# rizon_io.net
KiCad netlist of a schematic drawn in EAGLE
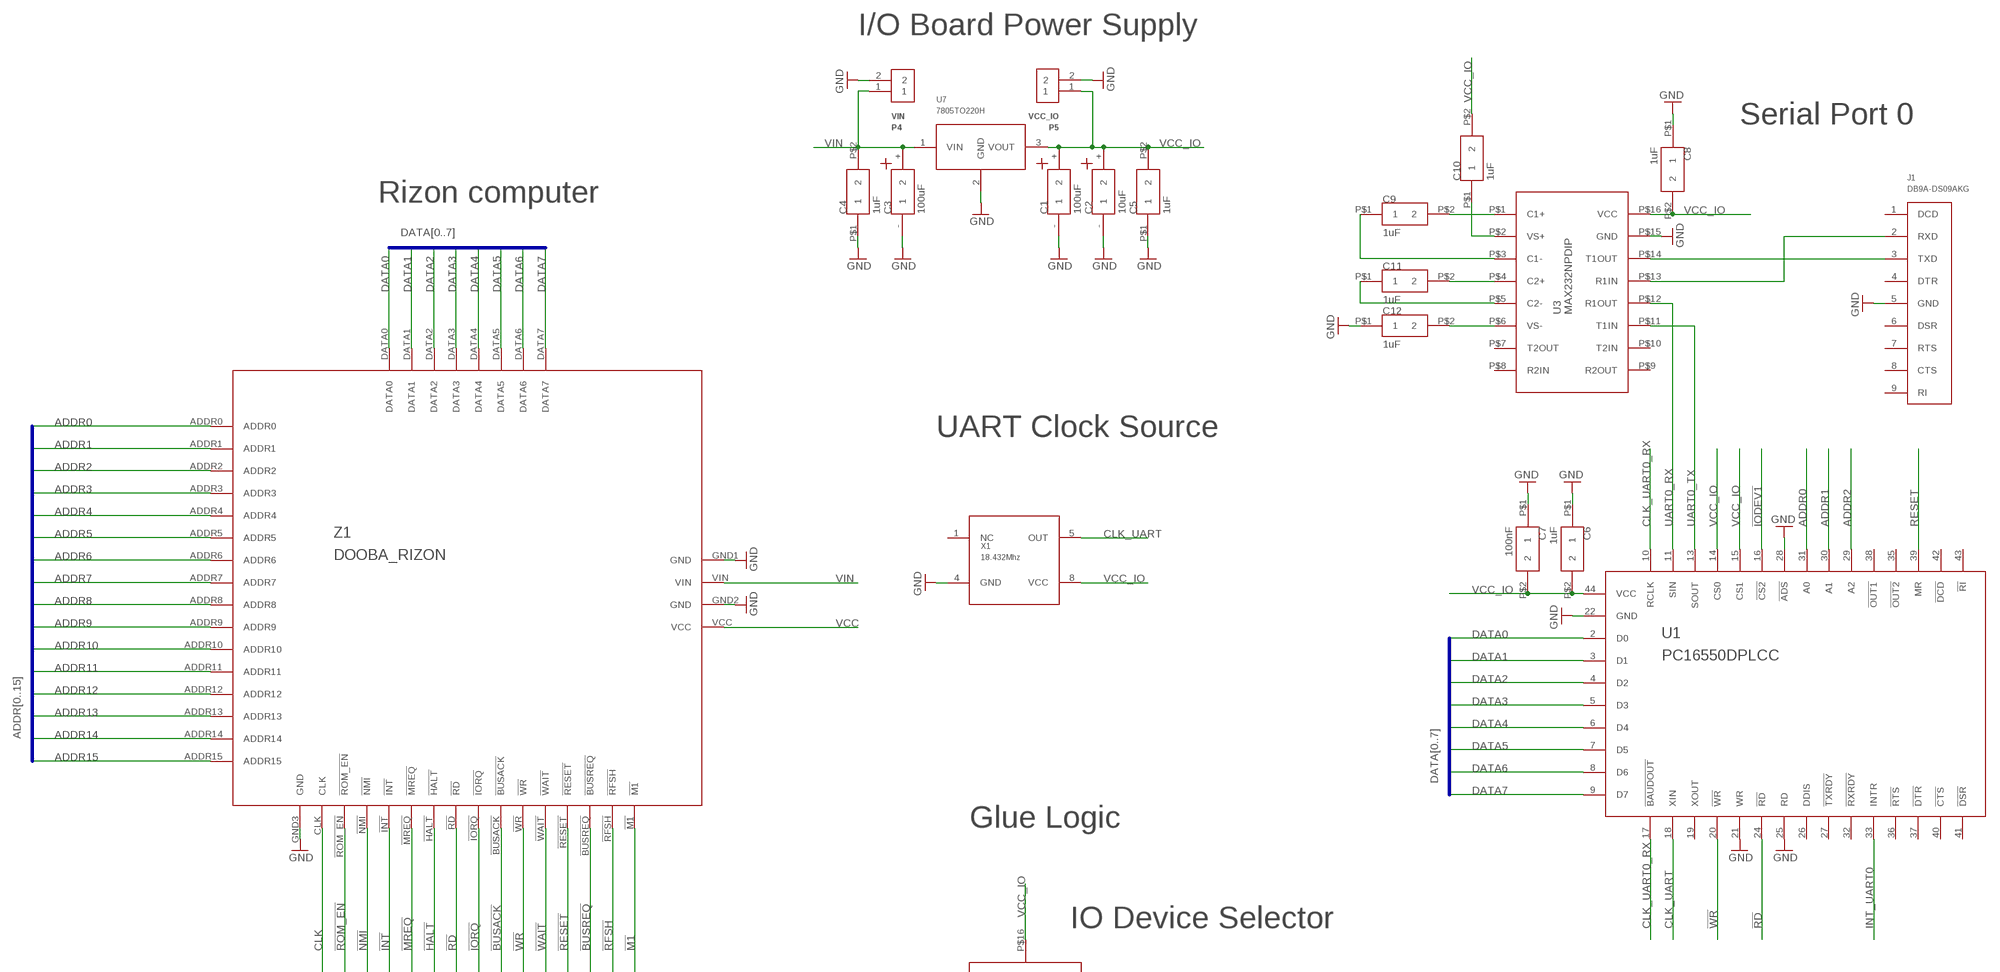
[diagram p0: schematic, sheet 1, part 1 of 3]
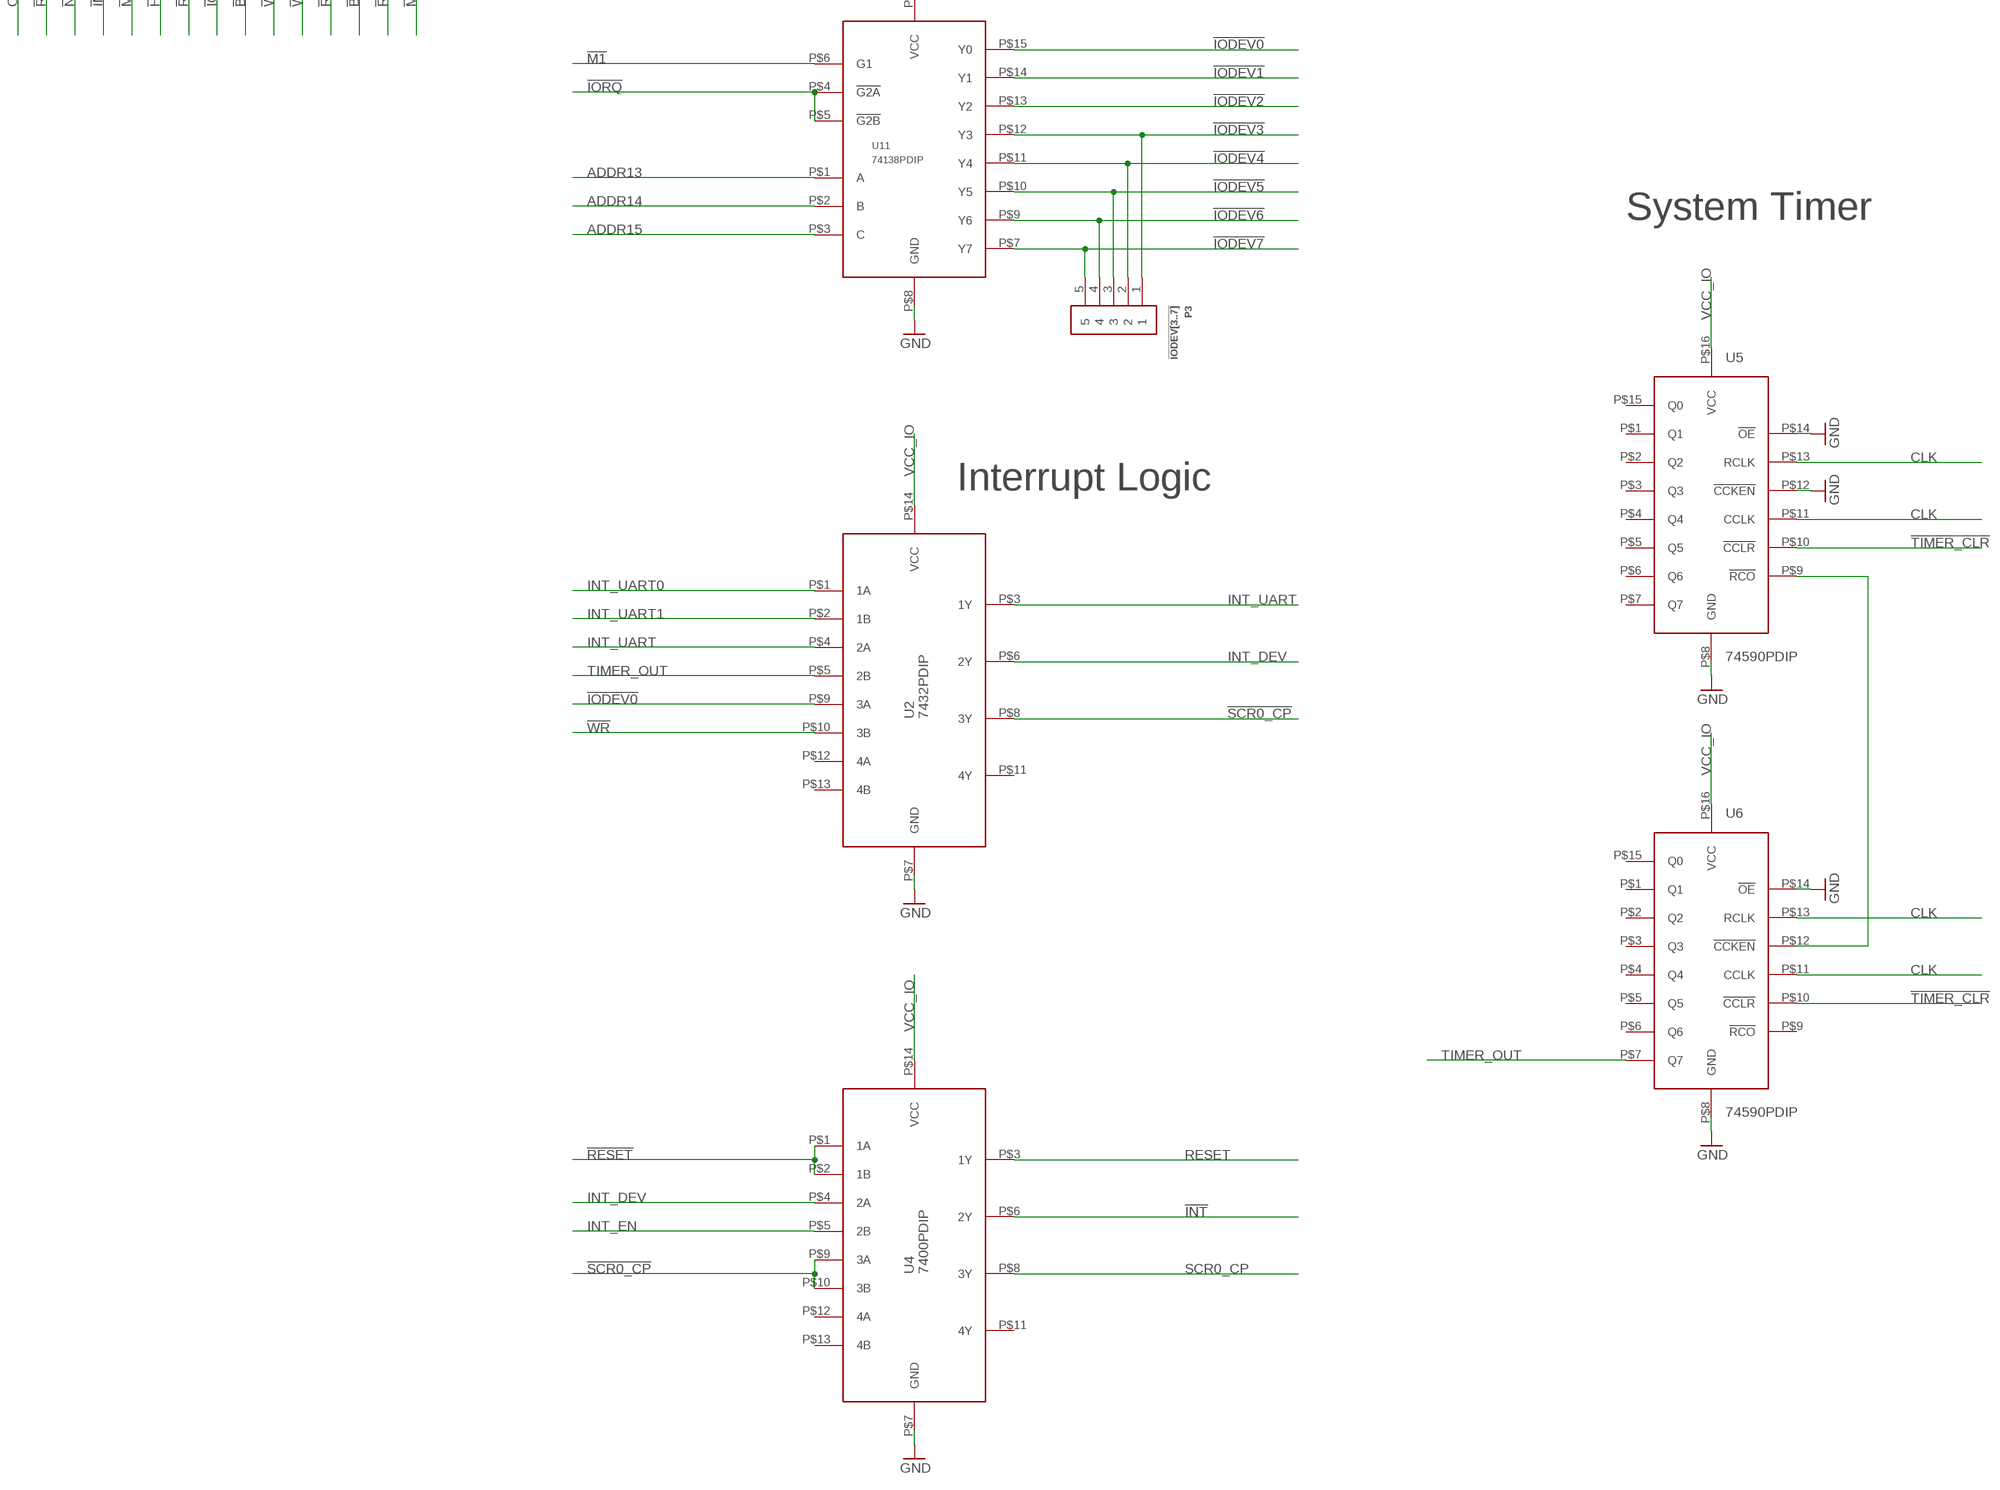
[diagram p1: schematic, sheet 1, part 2 of 3]
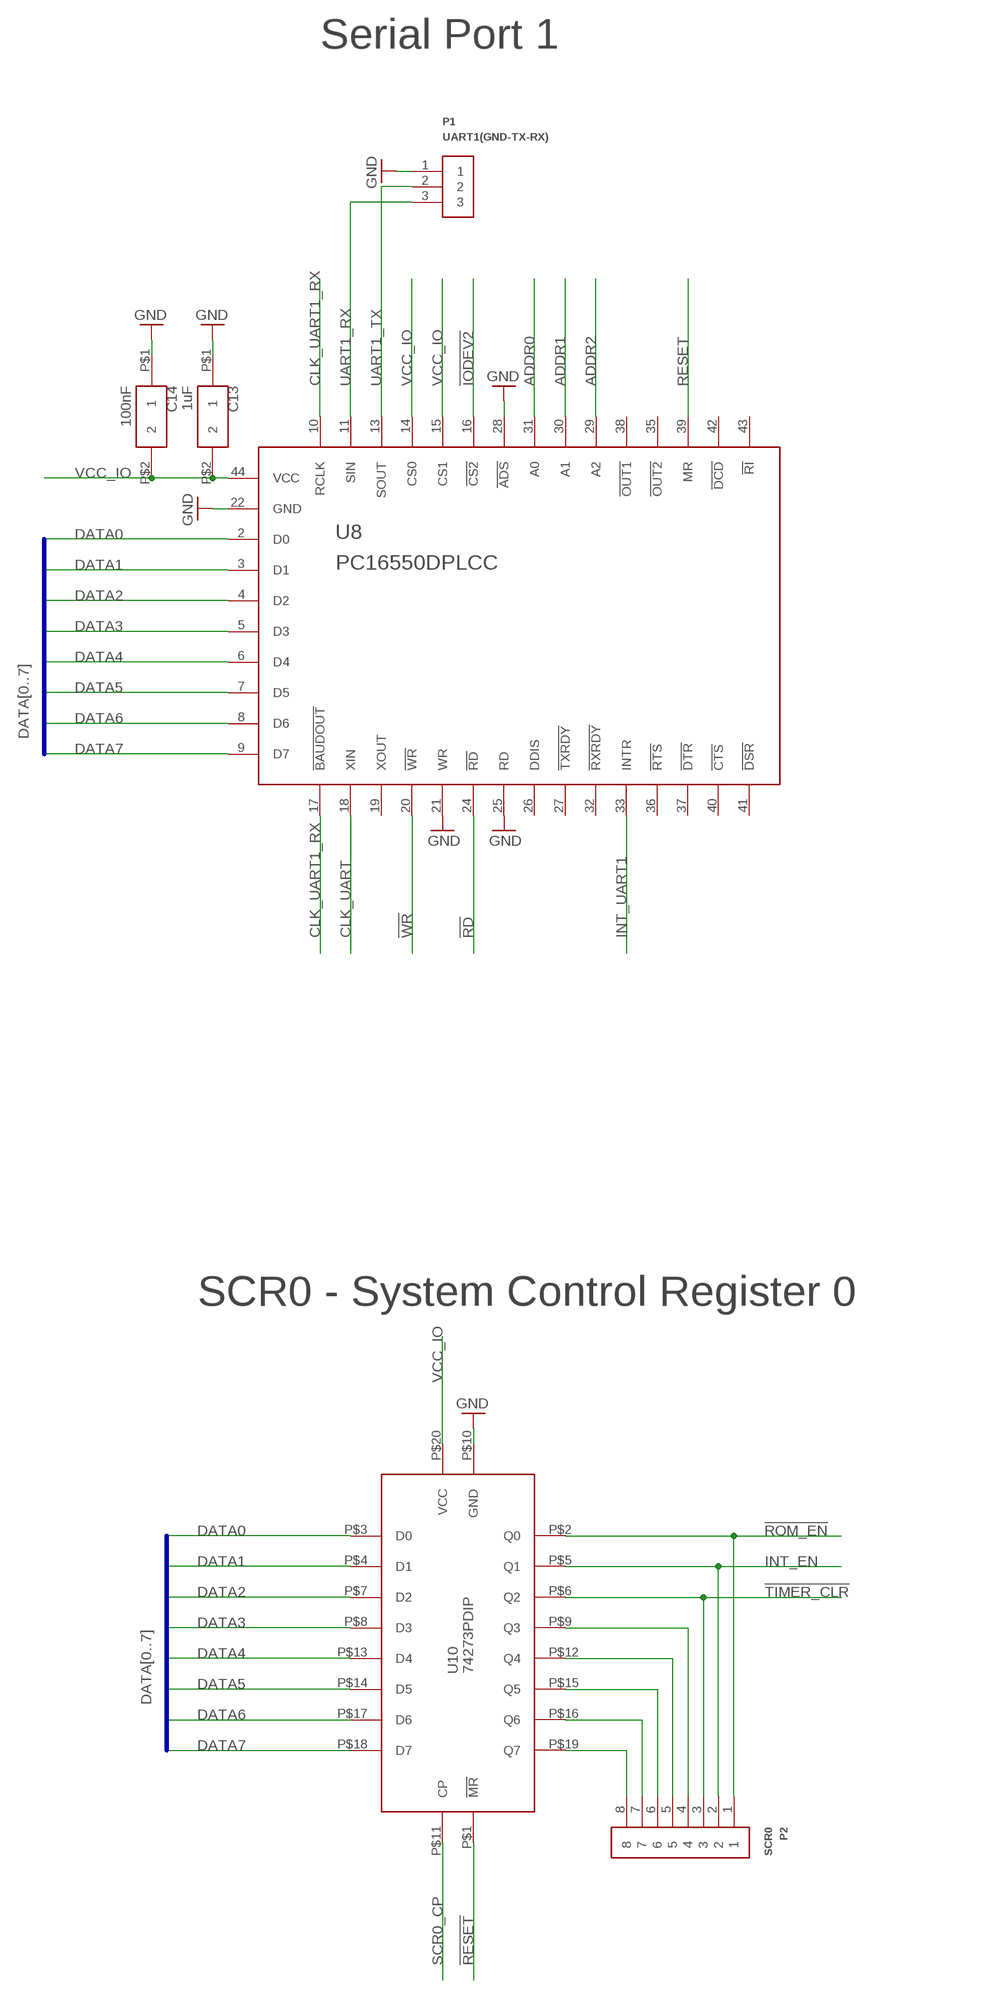
[diagram p2: schematic, sheet 1, part 3 of 3]

(export (version "E")
  (design (tool "Eeschema 10.0.6"))
  (components
    (comp (ref "C1")
      (value "100uF")
      (footprint "eagle-import:RADCAP_5MM")
      (libsource (lib "eagle-import") (part "CAP_POLARIZEDRAD_5MM"))
    )
    (comp (ref "C2")
      (value "10uF")
      (footprint "eagle-import:RADCAP_5MM")
      (libsource (lib "eagle-import") (part "CAP_POLARIZEDRAD_5MM"))
    )
    (comp (ref "C3")
      (value "100uF")
      (footprint "eagle-import:RADCAP_5MM")
      (libsource (lib "eagle-import") (part "CAP_POLARIZEDRAD_5MM"))
    )
    (comp (ref "C4")
      (value "1uF")
      (footprint "eagle-import:CAP_508")
      (libsource (lib "eagle-import") (part "CAP508"))
    )
    (comp (ref "C5")
      (value "1uF")
      (footprint "eagle-import:CAP_508")
      (libsource (lib "eagle-import") (part "CAP508"))
    )
    (comp (ref "C6")
      (value "1uF")
      (footprint "eagle-import:CAP_508")
      (libsource (lib "eagle-import") (part "CAP508"))
    )
    (comp (ref "C7")
      (value "100nF")
      (footprint "eagle-import:CAP_DISC")
      (libsource (lib "eagle-import") (part "CAPDISC"))
    )
    (comp (ref "C8")
      (value "1uF")
      (footprint "eagle-import:CAP_508")
      (libsource (lib "eagle-import") (part "CAP508"))
    )
    (comp (ref "C9")
      (value "1uF")
      (footprint "eagle-import:CAP_508")
      (libsource (lib "eagle-import") (part "CAP508"))
    )
    (comp (ref "C10")
      (value "1uF")
      (footprint "eagle-import:CAP_508")
      (libsource (lib "eagle-import") (part "CAP508"))
    )
    (comp (ref "C11")
      (value "1uF")
      (footprint "eagle-import:CAP_508")
      (libsource (lib "eagle-import") (part "CAP508"))
    )
    (comp (ref "C12")
      (value "1uF")
      (footprint "eagle-import:CAP_508")
      (libsource (lib "eagle-import") (part "CAP508"))
    )
    (comp (ref "C13")
      (value "1uF")
      (footprint "eagle-import:CAP_508")
      (libsource (lib "eagle-import") (part "CAP508"))
    )
    (comp (ref "C14")
      (value "100nF")
      (footprint "eagle-import:CAP_DISC")
      (libsource (lib "eagle-import") (part "CAPDISC"))
    )
    (comp (ref "J1")
      (value "DB9A-DS09AKG")
      (footprint "eagle-import:A-DS09AKG")
      (libsource (lib "eagle-import") (part "DB9A-DS09AKG"))
    )
    (comp (ref "P1")
      (value "UART1(GND-TX-RX)")
      (footprint "eagle-import:PIN_3")
      (libsource (lib "eagle-import") (part "PIN_3"))
    )
    (comp (ref "P2")
      (value "SCR0")
      (footprint "eagle-import:PIN_8")
      (libsource (lib "eagle-import") (part "PIN_8"))
    )
    (comp (ref "P3")
      (value "!IODEV[3..7]")
      (footprint "eagle-import:PIN_5")
      (libsource (lib "eagle-import") (part "PIN_5"))
    )
    (comp (ref "P4")
      (value "VIN")
      (footprint "eagle-import:PIN_2")
      (libsource (lib "eagle-import") (part "PIN_2"))
    )
    (comp (ref "P5")
      (value "VCC_IO")
      (footprint "eagle-import:PIN_2")
      (libsource (lib "eagle-import") (part "PIN_2"))
    )
    (comp (ref "U1")
      (value "PC16550DPLCC")
      (footprint "eagle-import:PLCC-S44-SOCKET")
      (libsource (lib "eagle-import") (part "PC16550DPLCC"))
    )
    (comp (ref "U2")
      (value "7432PDIP")
      (footprint "eagle-import:PDIP14")
      (libsource (lib "eagle-import") (part "7432PDIP"))
    )
    (comp (ref "U3")
      (value "MAX232NPDIP")
      (footprint "eagle-import:PDIP16")
      (libsource (lib "eagle-import") (part "MAX232NPDIP"))
    )
    (comp (ref "U4")
      (value "7400PDIP")
      (footprint "eagle-import:PDIP14")
      (libsource (lib "eagle-import") (part "7400PDIP"))
    )
    (comp (ref "U5")
      (value "74590PDIP")
      (footprint "eagle-import:PDIP16")
      (libsource (lib "eagle-import") (part "74590PDIP"))
    )
    (comp (ref "U6")
      (value "74590PDIP")
      (footprint "eagle-import:PDIP16")
      (libsource (lib "eagle-import") (part "74590PDIP"))
    )
    (comp (ref "U7")
      (value "7805TO220H")
      (footprint "eagle-import:TO220H")
      (libsource (lib "eagle-import") (part "7805TO220H"))
    )
    (comp (ref "U8")
      (value "PC16550DPLCC")
      (footprint "eagle-import:PLCC-S44-SOCKET")
      (libsource (lib "eagle-import") (part "PC16550DPLCC"))
    )
    (comp (ref "U10")
      (value "74273PDIP")
      (footprint "eagle-import:PDIP20")
      (libsource (lib "eagle-import") (part "74273PDIP"))
    )
    (comp (ref "U11")
      (value "74138PDIP")
      (footprint "eagle-import:PDIP16")
      (libsource (lib "eagle-import") (part "74138PDIP"))
    )
    (comp (ref "X1")
      (value "18.432Mhz")
      (footprint "eagle-import:OSC127")
      (libsource (lib "eagle-import") (part "OSC412.7"))
    )
    (comp (ref "Z1")
      (value "DOOBA_RIZON")
      (footprint "eagle-import:DOOBA_RIZON")
      (libsource (lib "eagle-import") (part "DOOBA_RIZON"))
    )
  )
  (nets
    (net (code "1") (name "/ADDR0") (class "Default")
      (node (ref "U1") (pin "31") (pinfunction "A0_31") (pintype "bidirectional"))
      (node (ref "U8") (pin "31") (pinfunction "A0_31") (pintype "bidirectional"))
      (node (ref "Z1") (pin "ADDR0") (pinfunction "ADDR0_ADDR0") (pintype "bidirectional"))
    )
    (net (code "2") (name "/ADDR1") (class "Default")
      (node (ref "U1") (pin "30") (pinfunction "A1_30") (pintype "bidirectional"))
      (node (ref "U8") (pin "30") (pinfunction "A1_30") (pintype "bidirectional"))
      (node (ref "Z1") (pin "ADDR1") (pinfunction "ADDR1_ADDR1") (pintype "bidirectional"))
    )
    (net (code "3") (name "/ADDR2") (class "Default")
      (node (ref "U1") (pin "29") (pinfunction "A2_29") (pintype "bidirectional"))
      (node (ref "U8") (pin "29") (pinfunction "A2_29") (pintype "bidirectional"))
      (node (ref "Z1") (pin "ADDR2") (pinfunction "ADDR2_ADDR2") (pintype "bidirectional"))
    )
    (net (code "4") (name "/ADDR3") (class "Default")
      (node (ref "Z1") (pin "ADDR3") (pinfunction "ADDR3_ADDR3") (pintype "bidirectional"))
    )
    (net (code "5") (name "/ADDR4") (class "Default")
      (node (ref "Z1") (pin "ADDR4") (pinfunction "ADDR4_ADDR4") (pintype "bidirectional"))
    )
    (net (code "6") (name "/ADDR5") (class "Default")
      (node (ref "Z1") (pin "ADDR5") (pinfunction "ADDR5_ADDR5") (pintype "bidirectional"))
    )
    (net (code "7") (name "/ADDR6") (class "Default")
      (node (ref "Z1") (pin "ADDR6") (pinfunction "ADDR6_ADDR6") (pintype "bidirectional"))
    )
    (net (code "8") (name "/ADDR7") (class "Default")
      (node (ref "Z1") (pin "ADDR7") (pinfunction "ADDR7_ADDR7") (pintype "bidirectional"))
    )
    (net (code "9") (name "/ADDR8") (class "Default")
      (node (ref "Z1") (pin "ADDR8") (pinfunction "ADDR8_ADDR8") (pintype "bidirectional"))
    )
    (net (code "10") (name "/ADDR9") (class "Default")
      (node (ref "Z1") (pin "ADDR9") (pinfunction "ADDR9_ADDR9") (pintype "bidirectional"))
    )
    (net (code "11") (name "/ADDR10") (class "Default")
      (node (ref "Z1") (pin "ADDR10") (pinfunction "ADDR10_ADDR10") (pintype "bidirectional"))
    )
    (net (code "12") (name "/ADDR11") (class "Default")
      (node (ref "Z1") (pin "ADDR11") (pinfunction "ADDR11_ADDR11") (pintype "bidirectional"))
    )
    (net (code "13") (name "/ADDR12") (class "Default")
      (node (ref "Z1") (pin "ADDR12") (pinfunction "ADDR12_ADDR12") (pintype "bidirectional"))
    )
    (net (code "14") (name "/ADDR13") (class "Default")
      (node (ref "U11") (pin "P$1") (pinfunction "A_P$1") (pintype "bidirectional"))
      (node (ref "Z1") (pin "ADDR13") (pinfunction "ADDR13_ADDR13") (pintype "bidirectional"))
    )
    (net (code "15") (name "/ADDR14") (class "Default")
      (node (ref "U11") (pin "P$2") (pinfunction "B_P$2") (pintype "bidirectional"))
      (node (ref "Z1") (pin "ADDR14") (pinfunction "ADDR14_ADDR14") (pintype "bidirectional"))
    )
    (net (code "16") (name "/ADDR15") (class "Default")
      (node (ref "U11") (pin "P$3") (pinfunction "C_P$3") (pintype "bidirectional"))
      (node (ref "Z1") (pin "ADDR15") (pinfunction "ADDR15_ADDR15") (pintype "bidirectional"))
    )
    (net (code "18") (name "/CLK") (class "Default")
      (node (ref "U5") (pin "P$11") (pinfunction "CCLK_P$11") (pintype "bidirectional"))
      (node (ref "U5") (pin "P$13") (pinfunction "RCLK_P$13") (pintype "bidirectional"))
      (node (ref "U6") (pin "P$11") (pinfunction "CCLK_P$11") (pintype "bidirectional"))
      (node (ref "U6") (pin "P$13") (pinfunction "RCLK_P$13") (pintype "bidirectional"))
      (node (ref "Z1") (pin "CLK") (pinfunction "CLK_CLK") (pintype "bidirectional"))
    )
    (net (code "19") (name "/CLK_UART") (class "Default")
      (node (ref "U1") (pin "18") (pinfunction "XIN_18") (pintype "bidirectional"))
      (node (ref "U8") (pin "18") (pinfunction "XIN_18") (pintype "bidirectional"))
      (node (ref "X1") (pin "5") (pinfunction "OUT_5") (pintype "bidirectional"))
    )
    (net (code "20") (name "/CLK_UART0_RX") (class "Default")
      (node (ref "U1") (pin "10") (pinfunction "RCLK_10") (pintype "bidirectional"))
      (node (ref "U1") (pin "17") (pinfunction "~{BAUDOUT}_17") (pintype "bidirectional"))
    )
    (net (code "21") (name "/CLK_UART1_RX") (class "Default")
      (node (ref "U8") (pin "10") (pinfunction "RCLK_10") (pintype "bidirectional"))
      (node (ref "U8") (pin "17") (pinfunction "~{BAUDOUT}_17") (pintype "bidirectional"))
    )
    (net (code "22") (name "/DATA0") (class "Default")
      (node (ref "U1") (pin "2") (pinfunction "D0_2") (pintype "bidirectional"))
      (node (ref "U10") (pin "P$3") (pinfunction "D0_P$3") (pintype "bidirectional"))
      (node (ref "U8") (pin "2") (pinfunction "D0_2") (pintype "bidirectional"))
      (node (ref "Z1") (pin "DATA0") (pinfunction "DATA0_DATA0") (pintype "bidirectional"))
    )
    (net (code "23") (name "/DATA1") (class "Default")
      (node (ref "U1") (pin "3") (pinfunction "D1_3") (pintype "bidirectional"))
      (node (ref "U10") (pin "P$4") (pinfunction "D1_P$4") (pintype "bidirectional"))
      (node (ref "U8") (pin "3") (pinfunction "D1_3") (pintype "bidirectional"))
      (node (ref "Z1") (pin "DATA1") (pinfunction "DATA1_DATA1") (pintype "bidirectional"))
    )
    (net (code "24") (name "/DATA2") (class "Default")
      (node (ref "U1") (pin "4") (pinfunction "D2_4") (pintype "bidirectional"))
      (node (ref "U10") (pin "P$7") (pinfunction "D2_P$7") (pintype "bidirectional"))
      (node (ref "U8") (pin "4") (pinfunction "D2_4") (pintype "bidirectional"))
      (node (ref "Z1") (pin "DATA2") (pinfunction "DATA2_DATA2") (pintype "bidirectional"))
    )
    (net (code "25") (name "/DATA3") (class "Default")
      (node (ref "U1") (pin "5") (pinfunction "D3_5") (pintype "bidirectional"))
      (node (ref "U10") (pin "P$8") (pinfunction "D3_P$8") (pintype "bidirectional"))
      (node (ref "U8") (pin "5") (pinfunction "D3_5") (pintype "bidirectional"))
      (node (ref "Z1") (pin "DATA3") (pinfunction "DATA3_DATA3") (pintype "bidirectional"))
    )
    (net (code "26") (name "/DATA4") (class "Default")
      (node (ref "U1") (pin "6") (pinfunction "D4_6") (pintype "bidirectional"))
      (node (ref "U10") (pin "P$13") (pinfunction "D4_P$13") (pintype "bidirectional"))
      (node (ref "U8") (pin "6") (pinfunction "D4_6") (pintype "bidirectional"))
      (node (ref "Z1") (pin "DATA4") (pinfunction "DATA4_DATA4") (pintype "bidirectional"))
    )
    (net (code "27") (name "/DATA5") (class "Default")
      (node (ref "U1") (pin "7") (pinfunction "D5_7") (pintype "bidirectional"))
      (node (ref "U10") (pin "P$14") (pinfunction "D5_P$14") (pintype "bidirectional"))
      (node (ref "U8") (pin "7") (pinfunction "D5_7") (pintype "bidirectional"))
      (node (ref "Z1") (pin "DATA5") (pinfunction "DATA5_DATA5") (pintype "bidirectional"))
    )
    (net (code "28") (name "/DATA6") (class "Default")
      (node (ref "U1") (pin "8") (pinfunction "D6_8") (pintype "bidirectional"))
      (node (ref "U10") (pin "P$17") (pinfunction "D6_P$17") (pintype "bidirectional"))
      (node (ref "U8") (pin "8") (pinfunction "D6_8") (pintype "bidirectional"))
      (node (ref "Z1") (pin "DATA6") (pinfunction "DATA6_DATA6") (pintype "bidirectional"))
    )
    (net (code "29") (name "/DATA7") (class "Default")
      (node (ref "U1") (pin "9") (pinfunction "D7_9") (pintype "bidirectional"))
      (node (ref "U10") (pin "P$18") (pinfunction "D7_P$18") (pintype "bidirectional"))
      (node (ref "U8") (pin "9") (pinfunction "D7_9") (pintype "bidirectional"))
      (node (ref "Z1") (pin "DATA7") (pinfunction "DATA7_DATA7") (pintype "bidirectional"))
    )
    (net (code "31") (name "/INT_DEV") (class "Default")
      (node (ref "U2") (pin "P$6") (pinfunction "2Y_P$6") (pintype "bidirectional"))
      (node (ref "U4") (pin "P$4") (pinfunction "2A_P$4") (pintype "bidirectional"))
    )
    (net (code "32") (name "/INT_EN") (class "Default")
      (node (ref "P2") (pin "2") (pinfunction "2_2") (pintype "bidirectional"))
      (node (ref "U10") (pin "P$5") (pinfunction "Q1_P$5") (pintype "bidirectional"))
      (node (ref "U4") (pin "P$5") (pinfunction "2B_P$5") (pintype "bidirectional"))
    )
    (net (code "33") (name "/INT_UART") (class "Default")
      (node (ref "U2") (pin "P$3") (pinfunction "1Y_P$3") (pintype "bidirectional"))
      (node (ref "U2") (pin "P$4") (pinfunction "2A_P$4") (pintype "bidirectional"))
    )
    (net (code "34") (name "/INT_UART0") (class "Default")
      (node (ref "U1") (pin "33") (pinfunction "INTR_33") (pintype "bidirectional"))
      (node (ref "U2") (pin "P$1") (pinfunction "1A_P$1") (pintype "bidirectional"))
    )
    (net (code "35") (name "/INT_UART1") (class "Default")
      (node (ref "U2") (pin "P$2") (pinfunction "1B_P$2") (pintype "bidirectional"))
      (node (ref "U8") (pin "33") (pinfunction "INTR_33") (pintype "bidirectional"))
    )
    (net (code "36") (name "/RESET") (class "Default")
      (node (ref "U1") (pin "39") (pinfunction "MR_39") (pintype "bidirectional"))
      (node (ref "U4") (pin "P$3") (pinfunction "1Y_P$3") (pintype "bidirectional"))
      (node (ref "U8") (pin "39") (pinfunction "MR_39") (pintype "bidirectional"))
    )
    (net (code "37") (name "/SCR0_CP") (class "Default")
      (node (ref "U10") (pin "P$11") (pinfunction "CP_P$11") (pintype "bidirectional"))
      (node (ref "U4") (pin "P$8") (pinfunction "3Y_P$8") (pintype "bidirectional"))
    )
    (net (code "38") (name "/TIMER_OUT") (class "Default")
      (node (ref "U2") (pin "P$5") (pinfunction "2B_P$5") (pintype "bidirectional"))
      (node (ref "U6") (pin "P$7") (pinfunction "Q7_P$7") (pintype "bidirectional"))
    )
    (net (code "39") (name "/UART0_RX") (class "Default")
      (node (ref "U1") (pin "11") (pinfunction "SIN_11") (pintype "bidirectional"))
      (node (ref "U3") (pin "P$12") (pinfunction "R1OUT_P$12") (pintype "bidirectional"))
    )
    (net (code "40") (name "/UART0_TX") (class "Default")
      (node (ref "U1") (pin "13") (pinfunction "SOUT_13") (pintype "bidirectional"))
      (node (ref "U3") (pin "P$11") (pinfunction "T1IN_P$11") (pintype "bidirectional"))
    )
    (net (code "41") (name "/UART1_RX") (class "Default")
      (node (ref "P1") (pin "3") (pinfunction "3_3") (pintype "bidirectional"))
      (node (ref "U8") (pin "11") (pinfunction "SIN_11") (pintype "bidirectional"))
    )
    (net (code "42") (name "/UART1_TX") (class "Default")
      (node (ref "P1") (pin "2") (pinfunction "2_2") (pintype "bidirectional"))
      (node (ref "U8") (pin "13") (pinfunction "SOUT_13") (pintype "bidirectional"))
    )
    (net (code "43") (name "/VCC") (class "Default")
      (node (ref "Z1") (pin "VCC") (pinfunction "VCC_VCC") (pintype "bidirectional"))
    )
    (net (code "44") (name "/VCC_IO") (class "Default")
      (node (ref "C1") (pin "+") (pinfunction "2_+") (pintype "bidirectional"))
      (node (ref "C10") (pin "P$2") (pinfunction "2_P$2") (pintype "bidirectional"))
      (node (ref "C13") (pin "P$2") (pinfunction "2_P$2") (pintype "bidirectional"))
      (node (ref "C14") (pin "P$2") (pinfunction "2_P$2") (pintype "bidirectional"))
      (node (ref "C2") (pin "+") (pinfunction "2_+") (pintype "bidirectional"))
      (node (ref "C5") (pin "P$2") (pinfunction "2_P$2") (pintype "bidirectional"))
      (node (ref "C6") (pin "P$2") (pinfunction "2_P$2") (pintype "bidirectional"))
      (node (ref "C7") (pin "P$2") (pinfunction "2_P$2") (pintype "bidirectional"))
      (node (ref "C8") (pin "P$2") (pinfunction "2_P$2") (pintype "bidirectional"))
      (node (ref "P5") (pin "1") (pinfunction "1_1") (pintype "bidirectional"))
      (node (ref "U1") (pin "14") (pinfunction "CS0_14") (pintype "bidirectional"))
      (node (ref "U1") (pin "15") (pinfunction "CS1_15") (pintype "bidirectional"))
      (node (ref "U1") (pin "44") (pinfunction "VCC_44") (pintype "bidirectional"))
      (node (ref "U10") (pin "P$20") (pinfunction "VCC_P$20") (pintype "bidirectional"))
      (node (ref "U11") (pin "P$16") (pinfunction "VCC_P$16") (pintype "bidirectional"))
      (node (ref "U2") (pin "P$14") (pinfunction "VCC_P$14") (pintype "bidirectional"))
      (node (ref "U3") (pin "P$16") (pinfunction "VCC_P$16") (pintype "bidirectional"))
      (node (ref "U4") (pin "P$14") (pinfunction "VCC_P$14") (pintype "bidirectional"))
      (node (ref "U5") (pin "P$16") (pinfunction "VCC_P$16") (pintype "bidirectional"))
      (node (ref "U6") (pin "P$16") (pinfunction "VCC_P$16") (pintype "bidirectional"))
      (node (ref "U7") (pin "3") (pinfunction "VOUT_3") (pintype "bidirectional"))
      (node (ref "U8") (pin "14") (pinfunction "CS0_14") (pintype "bidirectional"))
      (node (ref "U8") (pin "15") (pinfunction "CS1_15") (pintype "bidirectional"))
      (node (ref "U8") (pin "44") (pinfunction "VCC_44") (pintype "bidirectional"))
      (node (ref "X1") (pin "8") (pinfunction "VCC_8") (pintype "bidirectional"))
    )
    (net (code "45") (name "/VIN") (class "Default")
      (node (ref "C3") (pin "+") (pinfunction "2_+") (pintype "bidirectional"))
      (node (ref "C4") (pin "P$2") (pinfunction "2_P$2") (pintype "bidirectional"))
      (node (ref "P4") (pin "1") (pinfunction "1_1") (pintype "bidirectional"))
      (node (ref "U7") (pin "1") (pinfunction "VIN_1") (pintype "bidirectional"))
      (node (ref "Z1") (pin "VIN") (pinfunction "VIN_VIN") (pintype "bidirectional"))
    )
    (net (code "46") (name "/~{BUSACK}") (class "Default")
      (node (ref "Z1") (pin "!BUSACK") (pinfunction "~{BUSACK}_!BUSACK") (pintype "bidirectional"))
    )
    (net (code "47") (name "/~{BUSREQ}") (class "Default")
      (node (ref "Z1") (pin "!BUSREQ") (pinfunction "~{BUSREQ}_!BUSREQ") (pintype "bidirectional"))
    )
    (net (code "48") (name "/~{HALT}") (class "Default")
      (node (ref "Z1") (pin "!HALT") (pinfunction "~{HALT}_!HALT") (pintype "bidirectional"))
    )
    (net (code "49") (name "/~{INT}") (class "Default")
      (node (ref "U4") (pin "P$6") (pinfunction "2Y_P$6") (pintype "bidirectional"))
      (node (ref "Z1") (pin "!INT") (pinfunction "~{INT}_!INT") (pintype "bidirectional"))
    )
    (net (code "50") (name "/~{IODEV0}") (class "Default")
      (node (ref "U11") (pin "P$15") (pinfunction "Y0_P$15") (pintype "bidirectional"))
      (node (ref "U2") (pin "P$9") (pinfunction "3A_P$9") (pintype "bidirectional"))
    )
    (net (code "51") (name "/~{IODEV1}") (class "Default")
      (node (ref "U1") (pin "16") (pinfunction "~{CS2}_16") (pintype "bidirectional"))
      (node (ref "U11") (pin "P$14") (pinfunction "Y1_P$14") (pintype "bidirectional"))
    )
    (net (code "52") (name "/~{IODEV2}") (class "Default")
      (node (ref "U11") (pin "P$13") (pinfunction "Y2_P$13") (pintype "bidirectional"))
      (node (ref "U8") (pin "16") (pinfunction "~{CS2}_16") (pintype "bidirectional"))
    )
    (net (code "53") (name "/~{IODEV3}") (class "Default")
      (node (ref "P3") (pin "1") (pinfunction "1_1") (pintype "bidirectional"))
      (node (ref "U11") (pin "P$12") (pinfunction "Y3_P$12") (pintype "bidirectional"))
    )
    (net (code "54") (name "/~{IODEV4}") (class "Default")
      (node (ref "P3") (pin "2") (pinfunction "2_2") (pintype "bidirectional"))
      (node (ref "U11") (pin "P$11") (pinfunction "Y4_P$11") (pintype "bidirectional"))
    )
    (net (code "55") (name "/~{IODEV5}") (class "Default")
      (node (ref "P3") (pin "3") (pinfunction "3_3") (pintype "bidirectional"))
      (node (ref "U11") (pin "P$10") (pinfunction "Y5_P$10") (pintype "bidirectional"))
    )
    (net (code "56") (name "/~{IODEV6}") (class "Default")
      (node (ref "P3") (pin "4") (pinfunction "4_4") (pintype "bidirectional"))
      (node (ref "U11") (pin "P$9") (pinfunction "Y6_P$9") (pintype "bidirectional"))
    )
    (net (code "57") (name "/~{IODEV7}") (class "Default")
      (node (ref "P3") (pin "5") (pinfunction "5_5") (pintype "bidirectional"))
      (node (ref "U11") (pin "P$7") (pinfunction "Y7_P$7") (pintype "bidirectional"))
    )
    (net (code "58") (name "/~{IORQ}") (class "Default")
      (node (ref "U11") (pin "P$4") (pinfunction "~{G2A}_P$4") (pintype "bidirectional"))
      (node (ref "U11") (pin "P$5") (pinfunction "~{G2B}_P$5") (pintype "bidirectional"))
      (node (ref "Z1") (pin "!IORQ") (pinfunction "~{IORQ}_!IORQ") (pintype "bidirectional"))
    )
    (net (code "59") (name "/~{M1}") (class "Default")
      (node (ref "U11") (pin "P$6") (pinfunction "G1_P$6") (pintype "bidirectional"))
      (node (ref "Z1") (pin "!M1") (pinfunction "~{M1}_!M1") (pintype "bidirectional"))
    )
    (net (code "60") (name "/~{MREQ}") (class "Default")
      (node (ref "Z1") (pin "!MREQ") (pinfunction "~{MREQ}_!MREQ") (pintype "bidirectional"))
    )
    (net (code "61") (name "/~{NMI}") (class "Default")
      (node (ref "Z1") (pin "!NMI") (pinfunction "~{NMI}_!NMI") (pintype "bidirectional"))
    )
    (net (code "62") (name "/~{RD}") (class "Default")
      (node (ref "U1") (pin "24") (pinfunction "~{RD}_24") (pintype "bidirectional"))
      (node (ref "U8") (pin "24") (pinfunction "~{RD}_24") (pintype "bidirectional"))
      (node (ref "Z1") (pin "!RD") (pinfunction "~{RD}_!RD") (pintype "bidirectional"))
    )
    (net (code "63") (name "/~{RESET}") (class "Default")
      (node (ref "U10") (pin "P$1") (pinfunction "~{MR}_P$1") (pintype "bidirectional"))
      (node (ref "U4") (pin "P$1") (pinfunction "1A_P$1") (pintype "bidirectional"))
      (node (ref "U4") (pin "P$2") (pinfunction "1B_P$2") (pintype "bidirectional"))
      (node (ref "Z1") (pin "!RESET") (pinfunction "~{RESET}_!RESET") (pintype "bidirectional"))
    )
    (net (code "64") (name "/~{RFSH}") (class "Default")
      (node (ref "Z1") (pin "!RFSH") (pinfunction "~{RFSH}_!RFSH") (pintype "bidirectional"))
    )
    (net (code "65") (name "/~{ROM_EN}") (class "Default")
      (node (ref "P2") (pin "1") (pinfunction "1_1") (pintype "bidirectional"))
      (node (ref "U10") (pin "P$2") (pinfunction "Q0_P$2") (pintype "bidirectional"))
      (node (ref "Z1") (pin "!ROM_EN") (pinfunction "~{ROM_EN}_!ROM_EN") (pintype "bidirectional"))
    )
    (net (code "66") (name "/~{SCR0_CP}") (class "Default")
      (node (ref "U2") (pin "P$8") (pinfunction "3Y_P$8") (pintype "bidirectional"))
      (node (ref "U4") (pin "P$10") (pinfunction "3B_P$10") (pintype "bidirectional"))
      (node (ref "U4") (pin "P$9") (pinfunction "3A_P$9") (pintype "bidirectional"))
    )
    (net (code "67") (name "/~{TIMER_CLR}") (class "Default")
      (node (ref "P2") (pin "3") (pinfunction "3_3") (pintype "bidirectional"))
      (node (ref "U10") (pin "P$6") (pinfunction "Q2_P$6") (pintype "bidirectional"))
      (node (ref "U5") (pin "P$10") (pinfunction "~{CCLR}_P$10") (pintype "bidirectional"))
      (node (ref "U6") (pin "P$10") (pinfunction "~{CCLR}_P$10") (pintype "bidirectional"))
    )
    (net (code "68") (name "/~{WAIT}") (class "Default")
      (node (ref "Z1") (pin "!WAIT") (pinfunction "~{WAIT}_!WAIT") (pintype "bidirectional"))
    )
    (net (code "69") (name "/~{WR}") (class "Default")
      (node (ref "U1") (pin "20") (pinfunction "~{WR}_20") (pintype "bidirectional"))
      (node (ref "U2") (pin "P$10") (pinfunction "3B_P$10") (pintype "bidirectional"))
      (node (ref "U8") (pin "20") (pinfunction "~{WR}_20") (pintype "bidirectional"))
      (node (ref "Z1") (pin "!WR") (pinfunction "~{WR}_!WR") (pintype "bidirectional"))
    )
    (net (code "70") (name "GND") (class "Default")
      (node (ref "C1") (pin "-") (pinfunction "1_-") (pintype "bidirectional"))
      (node (ref "C12") (pin "P$1") (pinfunction "1_P$1") (pintype "bidirectional"))
      (node (ref "C13") (pin "P$1") (pinfunction "1_P$1") (pintype "bidirectional"))
      (node (ref "C14") (pin "P$1") (pinfunction "1_P$1") (pintype "bidirectional"))
      (node (ref "C2") (pin "-") (pinfunction "1_-") (pintype "bidirectional"))
      (node (ref "C3") (pin "-") (pinfunction "1_-") (pintype "bidirectional"))
      (node (ref "C4") (pin "P$1") (pinfunction "1_P$1") (pintype "bidirectional"))
      (node (ref "C5") (pin "P$1") (pinfunction "1_P$1") (pintype "bidirectional"))
      (node (ref "C6") (pin "P$1") (pinfunction "1_P$1") (pintype "bidirectional"))
      (node (ref "C7") (pin "P$1") (pinfunction "1_P$1") (pintype "bidirectional"))
      (node (ref "C8") (pin "P$1") (pinfunction "1_P$1") (pintype "bidirectional"))
      (node (ref "J1") (pin "5") (pinfunction "GND_5") (pintype "bidirectional"))
      (node (ref "P1") (pin "1") (pinfunction "1_1") (pintype "bidirectional"))
      (node (ref "P4") (pin "2") (pinfunction "2_2") (pintype "bidirectional"))
      (node (ref "P5") (pin "2") (pinfunction "2_2") (pintype "bidirectional"))
      (node (ref "U1") (pin "21") (pinfunction "WR_21") (pintype "bidirectional"))
      (node (ref "U1") (pin "22") (pinfunction "GND_22") (pintype "bidirectional"))
      (node (ref "U1") (pin "25") (pinfunction "RD_25") (pintype "bidirectional"))
      (node (ref "U1") (pin "28") (pinfunction "~{ADS}_28") (pintype "bidirectional"))
      (node (ref "U10") (pin "P$10") (pinfunction "GND_P$10") (pintype "bidirectional"))
      (node (ref "U11") (pin "P$8") (pinfunction "GND_P$8") (pintype "bidirectional"))
      (node (ref "U2") (pin "P$7") (pinfunction "GND_P$7") (pintype "bidirectional"))
      (node (ref "U3") (pin "P$15") (pinfunction "GND_P$15") (pintype "bidirectional"))
      (node (ref "U4") (pin "P$7") (pinfunction "GND_P$7") (pintype "bidirectional"))
      (node (ref "U5") (pin "P$12") (pinfunction "~{CCKEN}_P$12") (pintype "bidirectional"))
      (node (ref "U5") (pin "P$14") (pinfunction "~{OE}_P$14") (pintype "bidirectional"))
      (node (ref "U5") (pin "P$8") (pinfunction "GND_P$8") (pintype "bidirectional"))
      (node (ref "U6") (pin "P$14") (pinfunction "~{OE}_P$14") (pintype "bidirectional"))
      (node (ref "U6") (pin "P$8") (pinfunction "GND_P$8") (pintype "bidirectional"))
      (node (ref "U7") (pin "2") (pinfunction "GND_2") (pintype "bidirectional"))
      (node (ref "U8") (pin "21") (pinfunction "WR_21") (pintype "bidirectional"))
      (node (ref "U8") (pin "22") (pinfunction "GND_22") (pintype "bidirectional"))
      (node (ref "U8") (pin "25") (pinfunction "RD_25") (pintype "bidirectional"))
      (node (ref "U8") (pin "28") (pinfunction "~{ADS}_28") (pintype "bidirectional"))
      (node (ref "X1") (pin "4") (pinfunction "GND_4") (pintype "bidirectional"))
      (node (ref "Z1") (pin "GND1") (pinfunction "GND_GND1") (pintype "bidirectional"))
      (node (ref "Z1") (pin "GND2") (pinfunction "GND_GND2") (pintype "bidirectional"))
      (node (ref "Z1") (pin "GND3") (pinfunction "GND_GND3") (pintype "bidirectional"))
    )
    (net (code "71") (name "Net-(C9-1)") (class "Default")
      (node (ref "C9") (pin "P$1") (pinfunction "1_P$1") (pintype "bidirectional"))
      (node (ref "U3") (pin "P$3") (pinfunction "C1-_P$3") (pintype "bidirectional"))
    )
    (net (code "72") (name "Net-(C9-2)") (class "Default")
      (node (ref "C9") (pin "P$2") (pinfunction "2_P$2") (pintype "bidirectional"))
      (node (ref "U3") (pin "P$1") (pinfunction "C1+_P$1") (pintype "bidirectional"))
    )
    (net (code "73") (name "Net-(C10-1)") (class "Default")
      (node (ref "C10") (pin "P$1") (pinfunction "1_P$1") (pintype "bidirectional"))
      (node (ref "U3") (pin "P$2") (pinfunction "VS+_P$2") (pintype "bidirectional"))
    )
    (net (code "74") (name "Net-(C11-1)") (class "Default")
      (node (ref "C11") (pin "P$1") (pinfunction "1_P$1") (pintype "bidirectional"))
      (node (ref "U3") (pin "P$5") (pinfunction "C2-_P$5") (pintype "bidirectional"))
    )
    (net (code "75") (name "Net-(C11-2)") (class "Default")
      (node (ref "C11") (pin "P$2") (pinfunction "2_P$2") (pintype "bidirectional"))
      (node (ref "U3") (pin "P$4") (pinfunction "C2+_P$4") (pintype "bidirectional"))
    )
    (net (code "76") (name "Net-(C12-2)") (class "Default")
      (node (ref "C12") (pin "P$2") (pinfunction "2_P$2") (pintype "bidirectional"))
      (node (ref "U3") (pin "P$6") (pinfunction "VS-_P$6") (pintype "bidirectional"))
    )
    (net (code "77") (name "Net-(J1-RXD)") (class "Default")
      (node (ref "J1") (pin "2") (pinfunction "RXD_2") (pintype "bidirectional"))
      (node (ref "U3") (pin "P$13") (pinfunction "R1IN_P$13") (pintype "bidirectional"))
    )
    (net (code "78") (name "Net-(J1-TXD)") (class "Default")
      (node (ref "J1") (pin "3") (pinfunction "TXD_3") (pintype "bidirectional"))
      (node (ref "U3") (pin "P$14") (pinfunction "T1OUT_P$14") (pintype "bidirectional"))
    )
    (net (code "79") (name "Net-(U5-~{RCO})") (class "Default")
      (node (ref "U5") (pin "P$9") (pinfunction "~{RCO}_P$9") (pintype "bidirectional"))
      (node (ref "U6") (pin "P$12") (pinfunction "~{CCKEN}_P$12") (pintype "bidirectional"))
    )
    (net (code "80") (name "Net-(U10-Q3)") (class "Default")
      (node (ref "P2") (pin "4") (pinfunction "4_4") (pintype "bidirectional"))
      (node (ref "U10") (pin "P$9") (pinfunction "Q3_P$9") (pintype "bidirectional"))
    )
    (net (code "81") (name "Net-(U10-Q4)") (class "Default")
      (node (ref "P2") (pin "5") (pinfunction "5_5") (pintype "bidirectional"))
      (node (ref "U10") (pin "P$12") (pinfunction "Q4_P$12") (pintype "bidirectional"))
    )
    (net (code "82") (name "Net-(U10-Q5)") (class "Default")
      (node (ref "P2") (pin "6") (pinfunction "6_6") (pintype "bidirectional"))
      (node (ref "U10") (pin "P$15") (pinfunction "Q5_P$15") (pintype "bidirectional"))
    )
    (net (code "83") (name "Net-(U10-Q6)") (class "Default")
      (node (ref "P2") (pin "7") (pinfunction "7_7") (pintype "bidirectional"))
      (node (ref "U10") (pin "P$16") (pinfunction "Q6_P$16") (pintype "bidirectional"))
    )
    (net (code "84") (name "Net-(U10-Q7)") (class "Default")
      (node (ref "P2") (pin "8") (pinfunction "8_8") (pintype "bidirectional"))
      (node (ref "U10") (pin "P$19") (pinfunction "Q7_P$19") (pintype "bidirectional"))
    )
    (net (code "85") (name "unconnected-(J1-CTS-Pad8)") (class "Default")
      (node (ref "J1") (pin "8") (pinfunction "CTS_8") (pintype "bidirectional"))
    )
    (net (code "86") (name "unconnected-(J1-DCD-Pad1)") (class "Default")
      (node (ref "J1") (pin "1") (pinfunction "DCD_1") (pintype "bidirectional"))
    )
    (net (code "87") (name "unconnected-(J1-DSR-Pad6)") (class "Default")
      (node (ref "J1") (pin "6") (pinfunction "DSR_6") (pintype "bidirectional"))
    )
    (net (code "88") (name "unconnected-(J1-DTR-Pad4)") (class "Default")
      (node (ref "J1") (pin "4") (pinfunction "DTR_4") (pintype "bidirectional"))
    )
    (net (code "89") (name "unconnected-(J1-RI-Pad9)") (class "Default")
      (node (ref "J1") (pin "9") (pinfunction "RI_9") (pintype "bidirectional"))
    )
    (net (code "90") (name "unconnected-(J1-RTS-Pad7)") (class "Default")
      (node (ref "J1") (pin "7") (pinfunction "RTS_7") (pintype "bidirectional"))
    )
    (net (code "91") (name "unconnected-(U1-DDIS-Pad26)") (class "Default")
      (node (ref "U1") (pin "26") (pinfunction "DDIS_26") (pintype "bidirectional"))
    )
    (net (code "92") (name "unconnected-(U1-XOUT-Pad19)") (class "Default")
      (node (ref "U1") (pin "19") (pinfunction "XOUT_19") (pintype "bidirectional"))
    )
    (net (code "93") (name "unconnected-(U1-~{CTS}-Pad40)") (class "Default")
      (node (ref "U1") (pin "40") (pinfunction "~{CTS}_40") (pintype "bidirectional"))
    )
    (net (code "94") (name "unconnected-(U1-~{DCD}-Pad42)") (class "Default")
      (node (ref "U1") (pin "42") (pinfunction "~{DCD}_42") (pintype "bidirectional"))
    )
    (net (code "95") (name "unconnected-(U1-~{DSR}-Pad41)") (class "Default")
      (node (ref "U1") (pin "41") (pinfunction "~{DSR}_41") (pintype "bidirectional"))
    )
    (net (code "96") (name "unconnected-(U1-~{DTR}-Pad37)") (class "Default")
      (node (ref "U1") (pin "37") (pinfunction "~{DTR}_37") (pintype "bidirectional"))
    )
    (net (code "97") (name "unconnected-(U1-~{OUT1}-Pad38)") (class "Default")
      (node (ref "U1") (pin "38") (pinfunction "~{OUT1}_38") (pintype "bidirectional"))
    )
    (net (code "98") (name "unconnected-(U1-~{OUT2}-Pad35)") (class "Default")
      (node (ref "U1") (pin "35") (pinfunction "~{OUT2}_35") (pintype "bidirectional"))
    )
    (net (code "99") (name "unconnected-(U1-~{RI}-Pad43)") (class "Default")
      (node (ref "U1") (pin "43") (pinfunction "~{RI}_43") (pintype "bidirectional"))
    )
    (net (code "100") (name "unconnected-(U1-~{RTS}-Pad36)") (class "Default")
      (node (ref "U1") (pin "36") (pinfunction "~{RTS}_36") (pintype "bidirectional"))
    )
    (net (code "101") (name "unconnected-(U1-~{RXRDY}-Pad32)") (class "Default")
      (node (ref "U1") (pin "32") (pinfunction "~{RXRDY}_32") (pintype "bidirectional"))
    )
    (net (code "102") (name "unconnected-(U1-~{TXRDY}-Pad27)") (class "Default")
      (node (ref "U1") (pin "27") (pinfunction "~{TXRDY}_27") (pintype "bidirectional"))
    )
    (net (code "103") (name "unconnected-(U2-4A-PadP$12)") (class "Default")
      (node (ref "U2") (pin "P$12") (pinfunction "4A_P$12") (pintype "bidirectional"))
    )
    (net (code "104") (name "unconnected-(U2-4B-PadP$13)") (class "Default")
      (node (ref "U2") (pin "P$13") (pinfunction "4B_P$13") (pintype "bidirectional"))
    )
    (net (code "105") (name "unconnected-(U2-4Y-PadP$11)") (class "Default")
      (node (ref "U2") (pin "P$11") (pinfunction "4Y_P$11") (pintype "bidirectional"))
    )
    (net (code "106") (name "unconnected-(U3-R2IN-PadP$8)") (class "Default")
      (node (ref "U3") (pin "P$8") (pinfunction "R2IN_P$8") (pintype "bidirectional"))
    )
    (net (code "107") (name "unconnected-(U3-R2OUT-PadP$9)") (class "Default")
      (node (ref "U3") (pin "P$9") (pinfunction "R2OUT_P$9") (pintype "bidirectional"))
    )
    (net (code "108") (name "unconnected-(U3-T2IN-PadP$10)") (class "Default")
      (node (ref "U3") (pin "P$10") (pinfunction "T2IN_P$10") (pintype "bidirectional"))
    )
    (net (code "109") (name "unconnected-(U3-T2OUT-PadP$7)") (class "Default")
      (node (ref "U3") (pin "P$7") (pinfunction "T2OUT_P$7") (pintype "bidirectional"))
    )
    (net (code "110") (name "unconnected-(U4-4A-PadP$12)") (class "Default")
      (node (ref "U4") (pin "P$12") (pinfunction "4A_P$12") (pintype "bidirectional"))
    )
    (net (code "111") (name "unconnected-(U4-4B-PadP$13)") (class "Default")
      (node (ref "U4") (pin "P$13") (pinfunction "4B_P$13") (pintype "bidirectional"))
    )
    (net (code "112") (name "unconnected-(U4-4Y-PadP$11)") (class "Default")
      (node (ref "U4") (pin "P$11") (pinfunction "4Y_P$11") (pintype "bidirectional"))
    )
    (net (code "113") (name "unconnected-(U5-Q0-PadP$15)") (class "Default")
      (node (ref "U5") (pin "P$15") (pinfunction "Q0_P$15") (pintype "bidirectional"))
    )
    (net (code "114") (name "unconnected-(U5-Q1-PadP$1)") (class "Default")
      (node (ref "U5") (pin "P$1") (pinfunction "Q1_P$1") (pintype "bidirectional"))
    )
    (net (code "115") (name "unconnected-(U5-Q2-PadP$2)") (class "Default")
      (node (ref "U5") (pin "P$2") (pinfunction "Q2_P$2") (pintype "bidirectional"))
    )
    (net (code "116") (name "unconnected-(U5-Q3-PadP$3)") (class "Default")
      (node (ref "U5") (pin "P$3") (pinfunction "Q3_P$3") (pintype "bidirectional"))
    )
    (net (code "117") (name "unconnected-(U5-Q4-PadP$4)") (class "Default")
      (node (ref "U5") (pin "P$4") (pinfunction "Q4_P$4") (pintype "bidirectional"))
    )
    (net (code "118") (name "unconnected-(U5-Q5-PadP$5)") (class "Default")
      (node (ref "U5") (pin "P$5") (pinfunction "Q5_P$5") (pintype "bidirectional"))
    )
    (net (code "119") (name "unconnected-(U5-Q6-PadP$6)") (class "Default")
      (node (ref "U5") (pin "P$6") (pinfunction "Q6_P$6") (pintype "bidirectional"))
    )
    (net (code "120") (name "unconnected-(U5-Q7-PadP$7)") (class "Default")
      (node (ref "U5") (pin "P$7") (pinfunction "Q7_P$7") (pintype "bidirectional"))
    )
    (net (code "121") (name "unconnected-(U6-Q0-PadP$15)") (class "Default")
      (node (ref "U6") (pin "P$15") (pinfunction "Q0_P$15") (pintype "bidirectional"))
    )
    (net (code "122") (name "unconnected-(U6-Q1-PadP$1)") (class "Default")
      (node (ref "U6") (pin "P$1") (pinfunction "Q1_P$1") (pintype "bidirectional"))
    )
    (net (code "123") (name "unconnected-(U6-Q2-PadP$2)") (class "Default")
      (node (ref "U6") (pin "P$2") (pinfunction "Q2_P$2") (pintype "bidirectional"))
    )
    (net (code "124") (name "unconnected-(U6-Q3-PadP$3)") (class "Default")
      (node (ref "U6") (pin "P$3") (pinfunction "Q3_P$3") (pintype "bidirectional"))
    )
    (net (code "125") (name "unconnected-(U6-Q4-PadP$4)") (class "Default")
      (node (ref "U6") (pin "P$4") (pinfunction "Q4_P$4") (pintype "bidirectional"))
    )
    (net (code "126") (name "unconnected-(U6-Q5-PadP$5)") (class "Default")
      (node (ref "U6") (pin "P$5") (pinfunction "Q5_P$5") (pintype "bidirectional"))
    )
    (net (code "127") (name "unconnected-(U6-Q6-PadP$6)") (class "Default")
      (node (ref "U6") (pin "P$6") (pinfunction "Q6_P$6") (pintype "bidirectional"))
    )
    (net (code "128") (name "unconnected-(U6-~{RCO}-PadP$9)") (class "Default")
      (node (ref "U6") (pin "P$9") (pinfunction "~{RCO}_P$9") (pintype "bidirectional"))
    )
    (net (code "129") (name "unconnected-(U8-DDIS-Pad26)") (class "Default")
      (node (ref "U8") (pin "26") (pinfunction "DDIS_26") (pintype "bidirectional"))
    )
    (net (code "130") (name "unconnected-(U8-XOUT-Pad19)") (class "Default")
      (node (ref "U8") (pin "19") (pinfunction "XOUT_19") (pintype "bidirectional"))
    )
    (net (code "131") (name "unconnected-(U8-~{CTS}-Pad40)") (class "Default")
      (node (ref "U8") (pin "40") (pinfunction "~{CTS}_40") (pintype "bidirectional"))
    )
    (net (code "132") (name "unconnected-(U8-~{DCD}-Pad42)") (class "Default")
      (node (ref "U8") (pin "42") (pinfunction "~{DCD}_42") (pintype "bidirectional"))
    )
    (net (code "133") (name "unconnected-(U8-~{DSR}-Pad41)") (class "Default")
      (node (ref "U8") (pin "41") (pinfunction "~{DSR}_41") (pintype "bidirectional"))
    )
    (net (code "134") (name "unconnected-(U8-~{DTR}-Pad37)") (class "Default")
      (node (ref "U8") (pin "37") (pinfunction "~{DTR}_37") (pintype "bidirectional"))
    )
    (net (code "135") (name "unconnected-(U8-~{OUT1}-Pad38)") (class "Default")
      (node (ref "U8") (pin "38") (pinfunction "~{OUT1}_38") (pintype "bidirectional"))
    )
    (net (code "136") (name "unconnected-(U8-~{OUT2}-Pad35)") (class "Default")
      (node (ref "U8") (pin "35") (pinfunction "~{OUT2}_35") (pintype "bidirectional"))
    )
    (net (code "137") (name "unconnected-(U8-~{RI}-Pad43)") (class "Default")
      (node (ref "U8") (pin "43") (pinfunction "~{RI}_43") (pintype "bidirectional"))
    )
    (net (code "138") (name "unconnected-(U8-~{RTS}-Pad36)") (class "Default")
      (node (ref "U8") (pin "36") (pinfunction "~{RTS}_36") (pintype "bidirectional"))
    )
    (net (code "139") (name "unconnected-(U8-~{RXRDY}-Pad32)") (class "Default")
      (node (ref "U8") (pin "32") (pinfunction "~{RXRDY}_32") (pintype "bidirectional"))
    )
    (net (code "140") (name "unconnected-(U8-~{TXRDY}-Pad27)") (class "Default")
      (node (ref "U8") (pin "27") (pinfunction "~{TXRDY}_27") (pintype "bidirectional"))
    )
    (net (code "141") (name "unconnected-(X1-NC-Pad1)") (class "Default")
      (node (ref "X1") (pin "1") (pinfunction "NC_1") (pintype "bidirectional"))
    )
  )
)
